# Peripheral_Circuit_B.net
KiCad netlist of a schematic drawn in Altium Designer
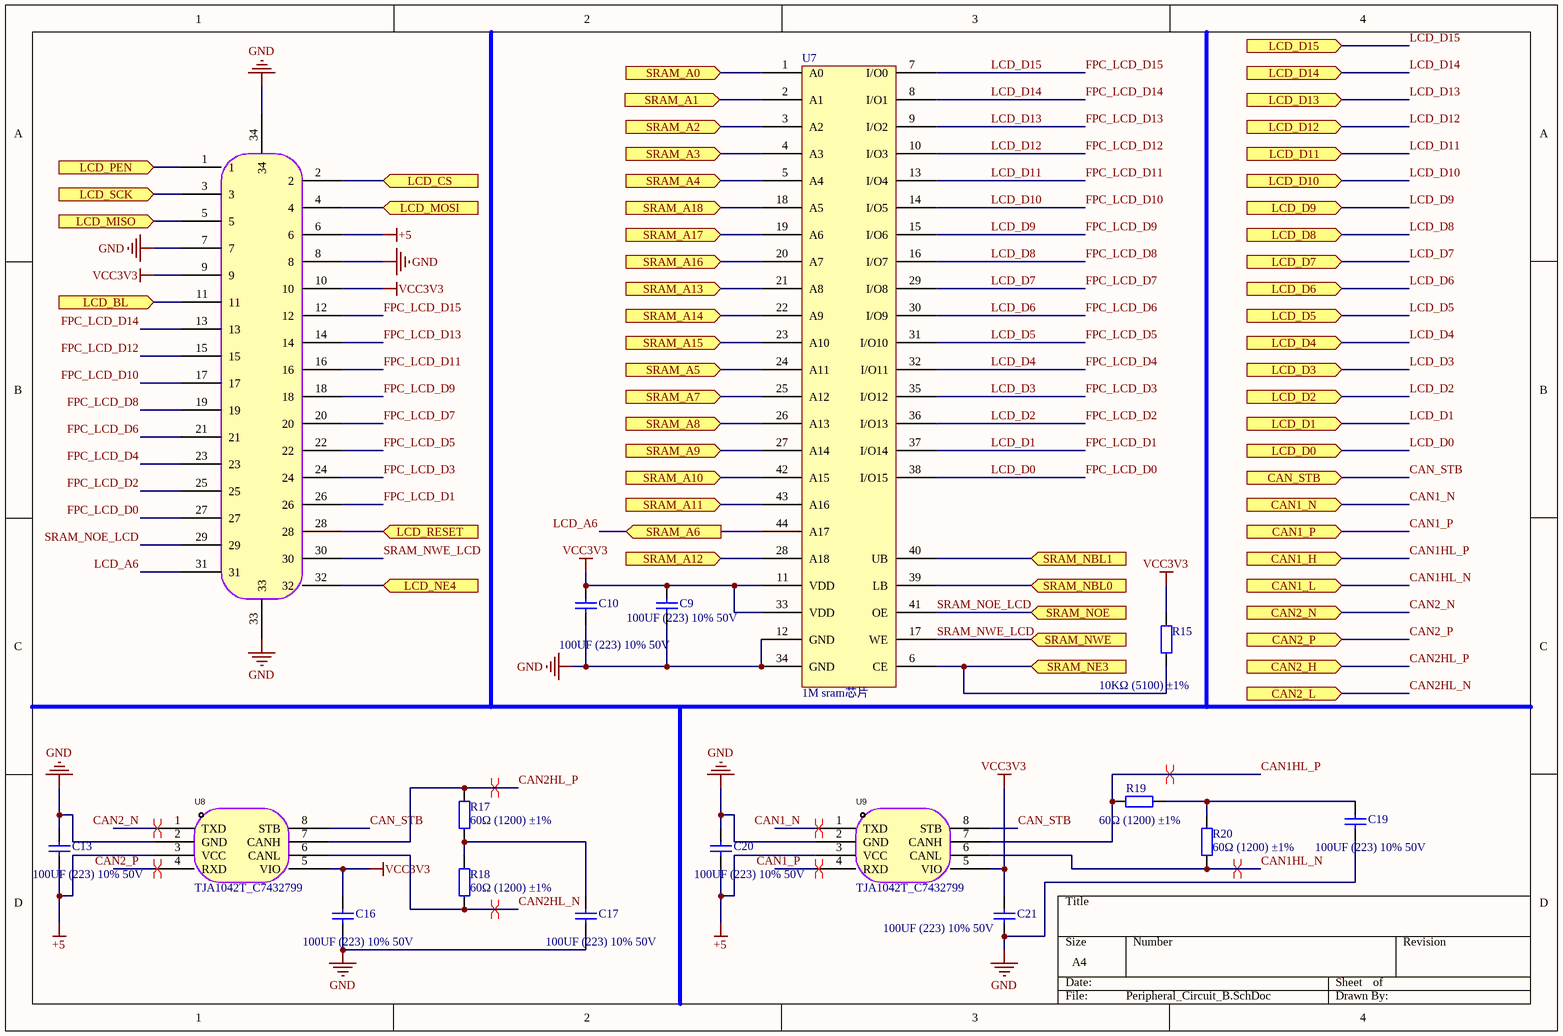
[diagram p0: Peripheral_Circuit_B.SchDoc]

(export (version "E")
  (design (tool "Eeschema 10.0.6"))
  (components
    (comp (ref "C9")
      (value "100UF (223) 10% 50V")
      (footprint "0805_C")
      (description "贴片电容")
      (libsource (lib "Miscellaneous Devices LC") (part "0805 22nF (223) 10% 50V"))
    )
    (comp (ref "C10")
      (value "100UF (223) 10% 50V")
      (footprint "0805_C")
      (description "贴片电容")
      (libsource (lib "Miscellaneous Devices LC") (part "0805 22nF (223) 10% 50V"))
    )
    (comp (ref "C13")
      (value "100UF (223) 10% 50V")
      (footprint "0805_C")
      (description "贴片电容")
      (libsource (lib "Miscellaneous Devices LC") (part "0805 22nF (223) 10% 50V"))
    )
    (comp (ref "C16")
      (value "100UF (223) 10% 50V")
      (footprint "0805_C")
      (description "贴片电容")
      (libsource (lib "Miscellaneous Devices LC") (part "0805 22nF (223) 10% 50V"))
    )
    (comp (ref "C17")
      (value "100UF (223) 10% 50V")
      (footprint "0805_C")
      (description "贴片电容")
      (libsource (lib "Miscellaneous Devices LC") (part "0805 22nF (223) 10% 50V"))
    )
    (comp (ref "C19")
      (value "100UF (223) 10% 50V")
      (footprint "0805_C")
      (description "贴片电容")
      (libsource (lib "Miscellaneous Devices LC") (part "0805 22nF (223) 10% 50V"))
    )
    (comp (ref "C20")
      (value "100UF (223) 10% 50V")
      (footprint "0805_C")
      (description "贴片电容")
      (libsource (lib "Miscellaneous Devices LC") (part "0805 22nF (223) 10% 50V"))
    )
    (comp (ref "C21")
      (value "100UF (223) 10% 50V")
      (footprint "0805_C")
      (description "贴片电容")
      (libsource (lib "Miscellaneous Devices LC") (part "0805 22nF (223) 10% 50V"))
    )
    (comp (ref "FPC1")
      (value "FPC-05F-32PH20")
      (footprint "FPC-SMD_32P-P0.50_XUNPU_FPC-05F-32PH20")
      (fields (field (name "MANUFACTURER") "XUNPU(讯普)"))
      (libsource (lib "EXTRA") (part "FPC-05F-32PH20"))
    )
    (comp (ref "R15")
      (value "10KΩ (5100) ±1%")
      (footprint "0805_R")
      (description "贴片电阻")
      (libsource (lib "Miscellaneous Devices LC") (part "0805 510Ω (5100) 1%"))
    )
    (comp (ref "R17")
      (value "60Ω (1200) ±1%")
      (footprint "0805_R")
      (description "贴片电阻")
      (libsource (lib "Miscellaneous Devices LC") (part "0805 120Ω (1200) 1%"))
    )
    (comp (ref "R18")
      (value "60Ω (1200) ±1%")
      (footprint "0805_R")
      (description "贴片电阻")
      (libsource (lib "Miscellaneous Devices LC") (part "0805 120Ω (1200) 1%"))
    )
    (comp (ref "R19")
      (value "60Ω (1200) ±1%")
      (footprint "0805_R")
      (description "贴片电阻")
      (libsource (lib "") (part "0805 120Ω (1200) 1%_1"))
    )
    (comp (ref "R20")
      (value "60Ω (1200) ±1%")
      (footprint "0805_R")
      (description "贴片电阻")
      (libsource (lib "Miscellaneous Devices LC") (part "0805 120Ω (1200) 1%"))
    )
    (comp (ref "U7")
      (value "1M sram芯片")
      (footprint "IS61LV51216")
      (description "外接SRAM芯片")
      (libsource (lib "EXTRA") (part "XM8A51216V33A"))
    )
    (comp (ref "U8")
      (value "TJA1042T_C7432799")
      (footprint "TJA1042")
      (fields (field (name "MANUFACTURER") "Tokmas(托克马斯)") (field (name "MANUFACTURER PART") "TJA1042T"))
      (libsource (lib "EXTRA") (part "TJA1042T_C7432799"))
    )
    (comp (ref "U9")
      (value "TJA1042T_C7432799")
      (footprint "TJA1042")
      (fields (field (name "MANUFACTURER") "Tokmas(托克马斯)") (field (name "MANUFACTURER PART") "TJA1042T"))
      (libsource (lib "EXTRA") (part "TJA1042T_C7432799"))
    )
  )
  (nets
    (net (code "1") (name "+5") (class "Default")
      (node (ref "C13") (pin "1") (pinfunction "1_1") (pintype "passive"))
      (node (ref "C20") (pin "1") (pinfunction "1_1") (pintype "passive"))
      (node (ref "FPC1") (pin "6") (pinfunction "6_6") (pintype "passive"))
      (node (ref "U8") (pin "3") (pinfunction "VCC_3") (pintype "passive"))
      (node (ref "U9") (pin "3") (pinfunction "VCC_3") (pintype "passive"))
    )
    (net (code "2") (name "/CAN1HL_N") (class "Default")
      (node (ref "R20") (pin "1") (pinfunction "1_1") (pintype "passive"))
      (node (ref "U9") (pin "6") (pinfunction "CANL_6") (pintype "passive"))
    )
    (net (code "3") (name "/CAN1HL_P") (class "Default")
      (node (ref "R19") (pin "2") (pinfunction "2_2") (pintype "passive"))
      (node (ref "U9") (pin "7") (pinfunction "CANH_7") (pintype "passive"))
    )
    (net (code "4") (name "/CAN1_N") (class "Default")
      (node (ref "U9") (pin "1") (pinfunction "TXD_1") (pintype "passive"))
    )
    (net (code "5") (name "/CAN1_P") (class "Default")
      (node (ref "U9") (pin "4") (pinfunction "RXD_4") (pintype "passive"))
    )
    (net (code "6") (name "/CAN2HL_N") (class "Default")
      (node (ref "R18") (pin "1") (pinfunction "1_1") (pintype "passive"))
      (node (ref "U8") (pin "6") (pinfunction "CANL_6") (pintype "passive"))
    )
    (net (code "7") (name "/CAN2HL_P") (class "Default")
      (node (ref "R17") (pin "2") (pinfunction "2_2") (pintype "passive"))
      (node (ref "U8") (pin "7") (pinfunction "CANH_7") (pintype "passive"))
    )
    (net (code "8") (name "/CAN2_N") (class "Default")
      (node (ref "U8") (pin "1") (pinfunction "TXD_1") (pintype "passive"))
    )
    (net (code "9") (name "/CAN2_P") (class "Default")
      (node (ref "U8") (pin "4") (pinfunction "RXD_4") (pintype "passive"))
    )
    (net (code "10") (name "/CAN_STB") (class "Default")
      (node (ref "U8") (pin "8") (pinfunction "STB_8") (pintype "passive"))
      (node (ref "U9") (pin "8") (pinfunction "STB_8") (pintype "passive"))
    )
    (net (code "11") (name "/FPC_LCD_D0") (class "Default")
      (node (ref "FPC1") (pin "27") (pinfunction "27_27") (pintype "passive"))
      (node (ref "U7") (pin "38") (pinfunction "I/O15_38") (pintype "passive"))
    )
    (net (code "12") (name "/FPC_LCD_D1") (class "Default")
      (node (ref "FPC1") (pin "26") (pinfunction "26_26") (pintype "passive"))
      (node (ref "U7") (pin "37") (pinfunction "I/O14_37") (pintype "passive"))
    )
    (net (code "13") (name "/FPC_LCD_D2") (class "Default")
      (node (ref "FPC1") (pin "25") (pinfunction "25_25") (pintype "passive"))
      (node (ref "U7") (pin "36") (pinfunction "I/O13_36") (pintype "passive"))
    )
    (net (code "14") (name "/FPC_LCD_D3") (class "Default")
      (node (ref "FPC1") (pin "24") (pinfunction "24_24") (pintype "passive"))
      (node (ref "U7") (pin "35") (pinfunction "I/O12_35") (pintype "passive"))
    )
    (net (code "15") (name "/FPC_LCD_D4") (class "Default")
      (node (ref "FPC1") (pin "23") (pinfunction "23_23") (pintype "passive"))
      (node (ref "U7") (pin "32") (pinfunction "I/O11_32") (pintype "passive"))
    )
    (net (code "16") (name "/FPC_LCD_D5") (class "Default")
      (node (ref "FPC1") (pin "22") (pinfunction "22_22") (pintype "passive"))
      (node (ref "U7") (pin "31") (pinfunction "I/O10_31") (pintype "passive"))
    )
    (net (code "17") (name "/FPC_LCD_D6") (class "Default")
      (node (ref "FPC1") (pin "21") (pinfunction "21_21") (pintype "passive"))
      (node (ref "U7") (pin "30") (pinfunction "I/O9_30") (pintype "passive"))
    )
    (net (code "18") (name "/FPC_LCD_D7") (class "Default")
      (node (ref "FPC1") (pin "20") (pinfunction "20_20") (pintype "passive"))
      (node (ref "U7") (pin "29") (pinfunction "I/O8_29") (pintype "passive"))
    )
    (net (code "19") (name "/FPC_LCD_D8") (class "Default")
      (node (ref "FPC1") (pin "19") (pinfunction "19_19") (pintype "passive"))
      (node (ref "U7") (pin "16") (pinfunction "I/O7_16") (pintype "passive"))
    )
    (net (code "20") (name "/FPC_LCD_D9") (class "Default")
      (node (ref "FPC1") (pin "18") (pinfunction "18_18") (pintype "passive"))
      (node (ref "U7") (pin "15") (pinfunction "I/O6_15") (pintype "passive"))
    )
    (net (code "21") (name "/FPC_LCD_D10") (class "Default")
      (node (ref "FPC1") (pin "17") (pinfunction "17_17") (pintype "passive"))
      (node (ref "U7") (pin "14") (pinfunction "I/O5_14") (pintype "passive"))
    )
    (net (code "22") (name "/FPC_LCD_D11") (class "Default")
      (node (ref "FPC1") (pin "16") (pinfunction "16_16") (pintype "passive"))
      (node (ref "U7") (pin "13") (pinfunction "I/O4_13") (pintype "passive"))
    )
    (net (code "23") (name "/FPC_LCD_D12") (class "Default")
      (node (ref "FPC1") (pin "15") (pinfunction "15_15") (pintype "passive"))
      (node (ref "U7") (pin "10") (pinfunction "I/O3_10") (pintype "passive"))
    )
    (net (code "24") (name "/FPC_LCD_D13") (class "Default")
      (node (ref "FPC1") (pin "14") (pinfunction "14_14") (pintype "passive"))
      (node (ref "U7") (pin "9") (pinfunction "I/O2_9") (pintype "passive"))
    )
    (net (code "25") (name "/FPC_LCD_D14") (class "Default")
      (node (ref "FPC1") (pin "13") (pinfunction "13_13") (pintype "passive"))
      (node (ref "U7") (pin "8") (pinfunction "I/O1_8") (pintype "passive"))
    )
    (net (code "26") (name "/FPC_LCD_D15") (class "Default")
      (node (ref "FPC1") (pin "12") (pinfunction "12_12") (pintype "passive"))
      (node (ref "U7") (pin "7") (pinfunction "I/O0_7") (pintype "passive"))
    )
    (net (code "27") (name "/LCD_A6") (class "Default")
      (node (ref "FPC1") (pin "31") (pinfunction "31_31") (pintype "passive"))
      (node (ref "U7") (pin "44") (pinfunction "A17_44") (pintype "passive"))
    )
    (net (code "28") (name "/LCD_BL") (class "Default")
      (node (ref "FPC1") (pin "11") (pinfunction "11_11") (pintype "passive"))
    )
    (net (code "29") (name "/LCD_CS") (class "Default")
      (node (ref "FPC1") (pin "2") (pinfunction "2_2") (pintype "passive"))
    )
    (net (code "30") (name "/LCD_MISO") (class "Default")
      (node (ref "FPC1") (pin "5") (pinfunction "5_5") (pintype "passive"))
    )
    (net (code "31") (name "/LCD_MOSI") (class "Default")
      (node (ref "FPC1") (pin "4") (pinfunction "4_4") (pintype "passive"))
    )
    (net (code "32") (name "/LCD_NE4") (class "Default")
      (node (ref "FPC1") (pin "32") (pinfunction "32_32") (pintype "passive"))
    )
    (net (code "33") (name "/LCD_PEN") (class "Default")
      (node (ref "FPC1") (pin "1") (pinfunction "1_1") (pintype "passive"))
    )
    (net (code "34") (name "/LCD_RESET") (class "Default")
      (node (ref "FPC1") (pin "28") (pinfunction "28_28") (pintype "passive"))
    )
    (net (code "35") (name "/LCD_SCK") (class "Default")
      (node (ref "FPC1") (pin "3") (pinfunction "3_3") (pintype "passive"))
    )
    (net (code "36") (name "/SRAM_A0") (class "Default")
      (node (ref "U7") (pin "1") (pinfunction "A0_1") (pintype "passive"))
    )
    (net (code "37") (name "/SRAM_A1") (class "Default")
      (node (ref "U7") (pin "2") (pinfunction "A1_2") (pintype "passive"))
    )
    (net (code "38") (name "/SRAM_A2") (class "Default")
      (node (ref "U7") (pin "3") (pinfunction "A2_3") (pintype "passive"))
    )
    (net (code "39") (name "/SRAM_A3") (class "Default")
      (node (ref "U7") (pin "4") (pinfunction "A3_4") (pintype "passive"))
    )
    (net (code "40") (name "/SRAM_A4") (class "Default")
      (node (ref "U7") (pin "5") (pinfunction "A4_5") (pintype "passive"))
    )
    (net (code "41") (name "/SRAM_A5") (class "Default")
      (node (ref "U7") (pin "24") (pinfunction "A11_24") (pintype "passive"))
    )
    (net (code "42") (name "/SRAM_A7") (class "Default")
      (node (ref "U7") (pin "25") (pinfunction "A12_25") (pintype "passive"))
    )
    (net (code "43") (name "/SRAM_A8") (class "Default")
      (node (ref "U7") (pin "26") (pinfunction "A13_26") (pintype "passive"))
    )
    (net (code "44") (name "/SRAM_A9") (class "Default")
      (node (ref "U7") (pin "27") (pinfunction "A14_27") (pintype "passive"))
    )
    (net (code "45") (name "/SRAM_A10") (class "Default")
      (node (ref "U7") (pin "42") (pinfunction "A15_42") (pintype "passive"))
    )
    (net (code "46") (name "/SRAM_A11") (class "Default")
      (node (ref "U7") (pin "43") (pinfunction "A16_43") (pintype "passive"))
    )
    (net (code "47") (name "/SRAM_A12") (class "Default")
      (node (ref "U7") (pin "28") (pinfunction "A18_28") (pintype "passive"))
    )
    (net (code "48") (name "/SRAM_A13") (class "Default")
      (node (ref "U7") (pin "21") (pinfunction "A8_21") (pintype "passive"))
    )
    (net (code "49") (name "/SRAM_A14") (class "Default")
      (node (ref "U7") (pin "22") (pinfunction "A9_22") (pintype "passive"))
    )
    (net (code "50") (name "/SRAM_A15") (class "Default")
      (node (ref "U7") (pin "23") (pinfunction "A10_23") (pintype "passive"))
    )
    (net (code "51") (name "/SRAM_A16") (class "Default")
      (node (ref "U7") (pin "20") (pinfunction "A7_20") (pintype "passive"))
    )
    (net (code "52") (name "/SRAM_A17") (class "Default")
      (node (ref "U7") (pin "19") (pinfunction "A6_19") (pintype "passive"))
    )
    (net (code "53") (name "/SRAM_A18") (class "Default")
      (node (ref "U7") (pin "18") (pinfunction "A5_18") (pintype "passive"))
    )
    (net (code "54") (name "/SRAM_NBL0") (class "Default")
      (node (ref "U7") (pin "39") (pinfunction "LB_39") (pintype "passive"))
    )
    (net (code "55") (name "/SRAM_NBL1") (class "Default")
      (node (ref "U7") (pin "40") (pinfunction "UB_40") (pintype "passive"))
    )
    (net (code "56") (name "/SRAM_NE3") (class "Default")
      (node (ref "R15") (pin "1") (pinfunction "1_1") (pintype "passive"))
      (node (ref "U7") (pin "6") (pinfunction "CE_6") (pintype "passive"))
    )
    (net (code "57") (name "/SRAM_NOE_LCD") (class "Default")
      (node (ref "FPC1") (pin "29") (pinfunction "29_29") (pintype "passive"))
      (node (ref "U7") (pin "41") (pinfunction "OE_41") (pintype "passive"))
    )
    (net (code "58") (name "/SRAM_NWE_LCD") (class "Default")
      (node (ref "FPC1") (pin "30") (pinfunction "30_30") (pintype "passive"))
      (node (ref "U7") (pin "17") (pinfunction "WE_17") (pintype "passive"))
    )
    (net (code "59") (name "GND") (class "Default")
      (node (ref "C10") (pin "1") (pinfunction "1_1") (pintype "passive"))
      (node (ref "C13") (pin "2") (pinfunction "2_2") (pintype "passive"))
      (node (ref "C16") (pin "1") (pinfunction "1_1") (pintype "passive"))
      (node (ref "C17") (pin "1") (pinfunction "1_1") (pintype "passive"))
      (node (ref "C19") (pin "1") (pinfunction "1_1") (pintype "passive"))
      (node (ref "C20") (pin "2") (pinfunction "2_2") (pintype "passive"))
      (node (ref "C21") (pin "1") (pinfunction "1_1") (pintype "passive"))
      (node (ref "C9") (pin "1") (pinfunction "1_1") (pintype "passive"))
      (node (ref "FPC1") (pin "33") (pinfunction "33_33") (pintype "passive"))
      (node (ref "FPC1") (pin "34") (pinfunction "34_34") (pintype "passive"))
      (node (ref "FPC1") (pin "7") (pinfunction "7_7") (pintype "passive"))
      (node (ref "FPC1") (pin "8") (pinfunction "8_8") (pintype "passive"))
      (node (ref "U7") (pin "12") (pinfunction "GND_12") (pintype "passive"))
      (node (ref "U7") (pin "34") (pinfunction "GND_34") (pintype "passive"))
      (node (ref "U8") (pin "2") (pinfunction "GND_2") (pintype "passive"))
      (node (ref "U9") (pin "2") (pinfunction "GND_2") (pintype "passive"))
    )
    (net (code "60") (name "Net-(C17-Pad2)") (class "Default")
      (node (ref "C17") (pin "2") (pinfunction "2_2") (pintype "passive"))
      (node (ref "R17") (pin "1") (pinfunction "1_1") (pintype "passive"))
      (node (ref "R18") (pin "2") (pinfunction "2_2") (pintype "passive"))
    )
    (net (code "61") (name "Net-(C19-Pad2)") (class "Default")
      (node (ref "C19") (pin "2") (pinfunction "2_2") (pintype "passive"))
      (node (ref "R19") (pin "1") (pinfunction "1_1") (pintype "passive"))
      (node (ref "R20") (pin "2") (pinfunction "2_2") (pintype "passive"))
    )
    (net (code "62") (name "VCC3V3") (class "Default")
      (node (ref "C10") (pin "2") (pinfunction "2_2") (pintype "passive"))
      (node (ref "C16") (pin "2") (pinfunction "2_2") (pintype "passive"))
      (node (ref "C21") (pin "2") (pinfunction "2_2") (pintype "passive"))
      (node (ref "C9") (pin "2") (pinfunction "2_2") (pintype "passive"))
      (node (ref "FPC1") (pin "10") (pinfunction "10_10") (pintype "passive"))
      (node (ref "FPC1") (pin "9") (pinfunction "9_9") (pintype "passive"))
      (node (ref "R15") (pin "2") (pinfunction "2_2") (pintype "passive"))
      (node (ref "U7") (pin "11") (pinfunction "VDD_11") (pintype "passive"))
      (node (ref "U7") (pin "33") (pinfunction "VDD_33") (pintype "passive"))
      (node (ref "U8") (pin "5") (pinfunction "VIO_5") (pintype "passive"))
      (node (ref "U9") (pin "5") (pinfunction "VIO_5") (pintype "passive"))
    )
  )
)
